# SCH_gaussian_cheap_2025-03-23.net
KiCad netlist of a schematic drawn in EasyEDA
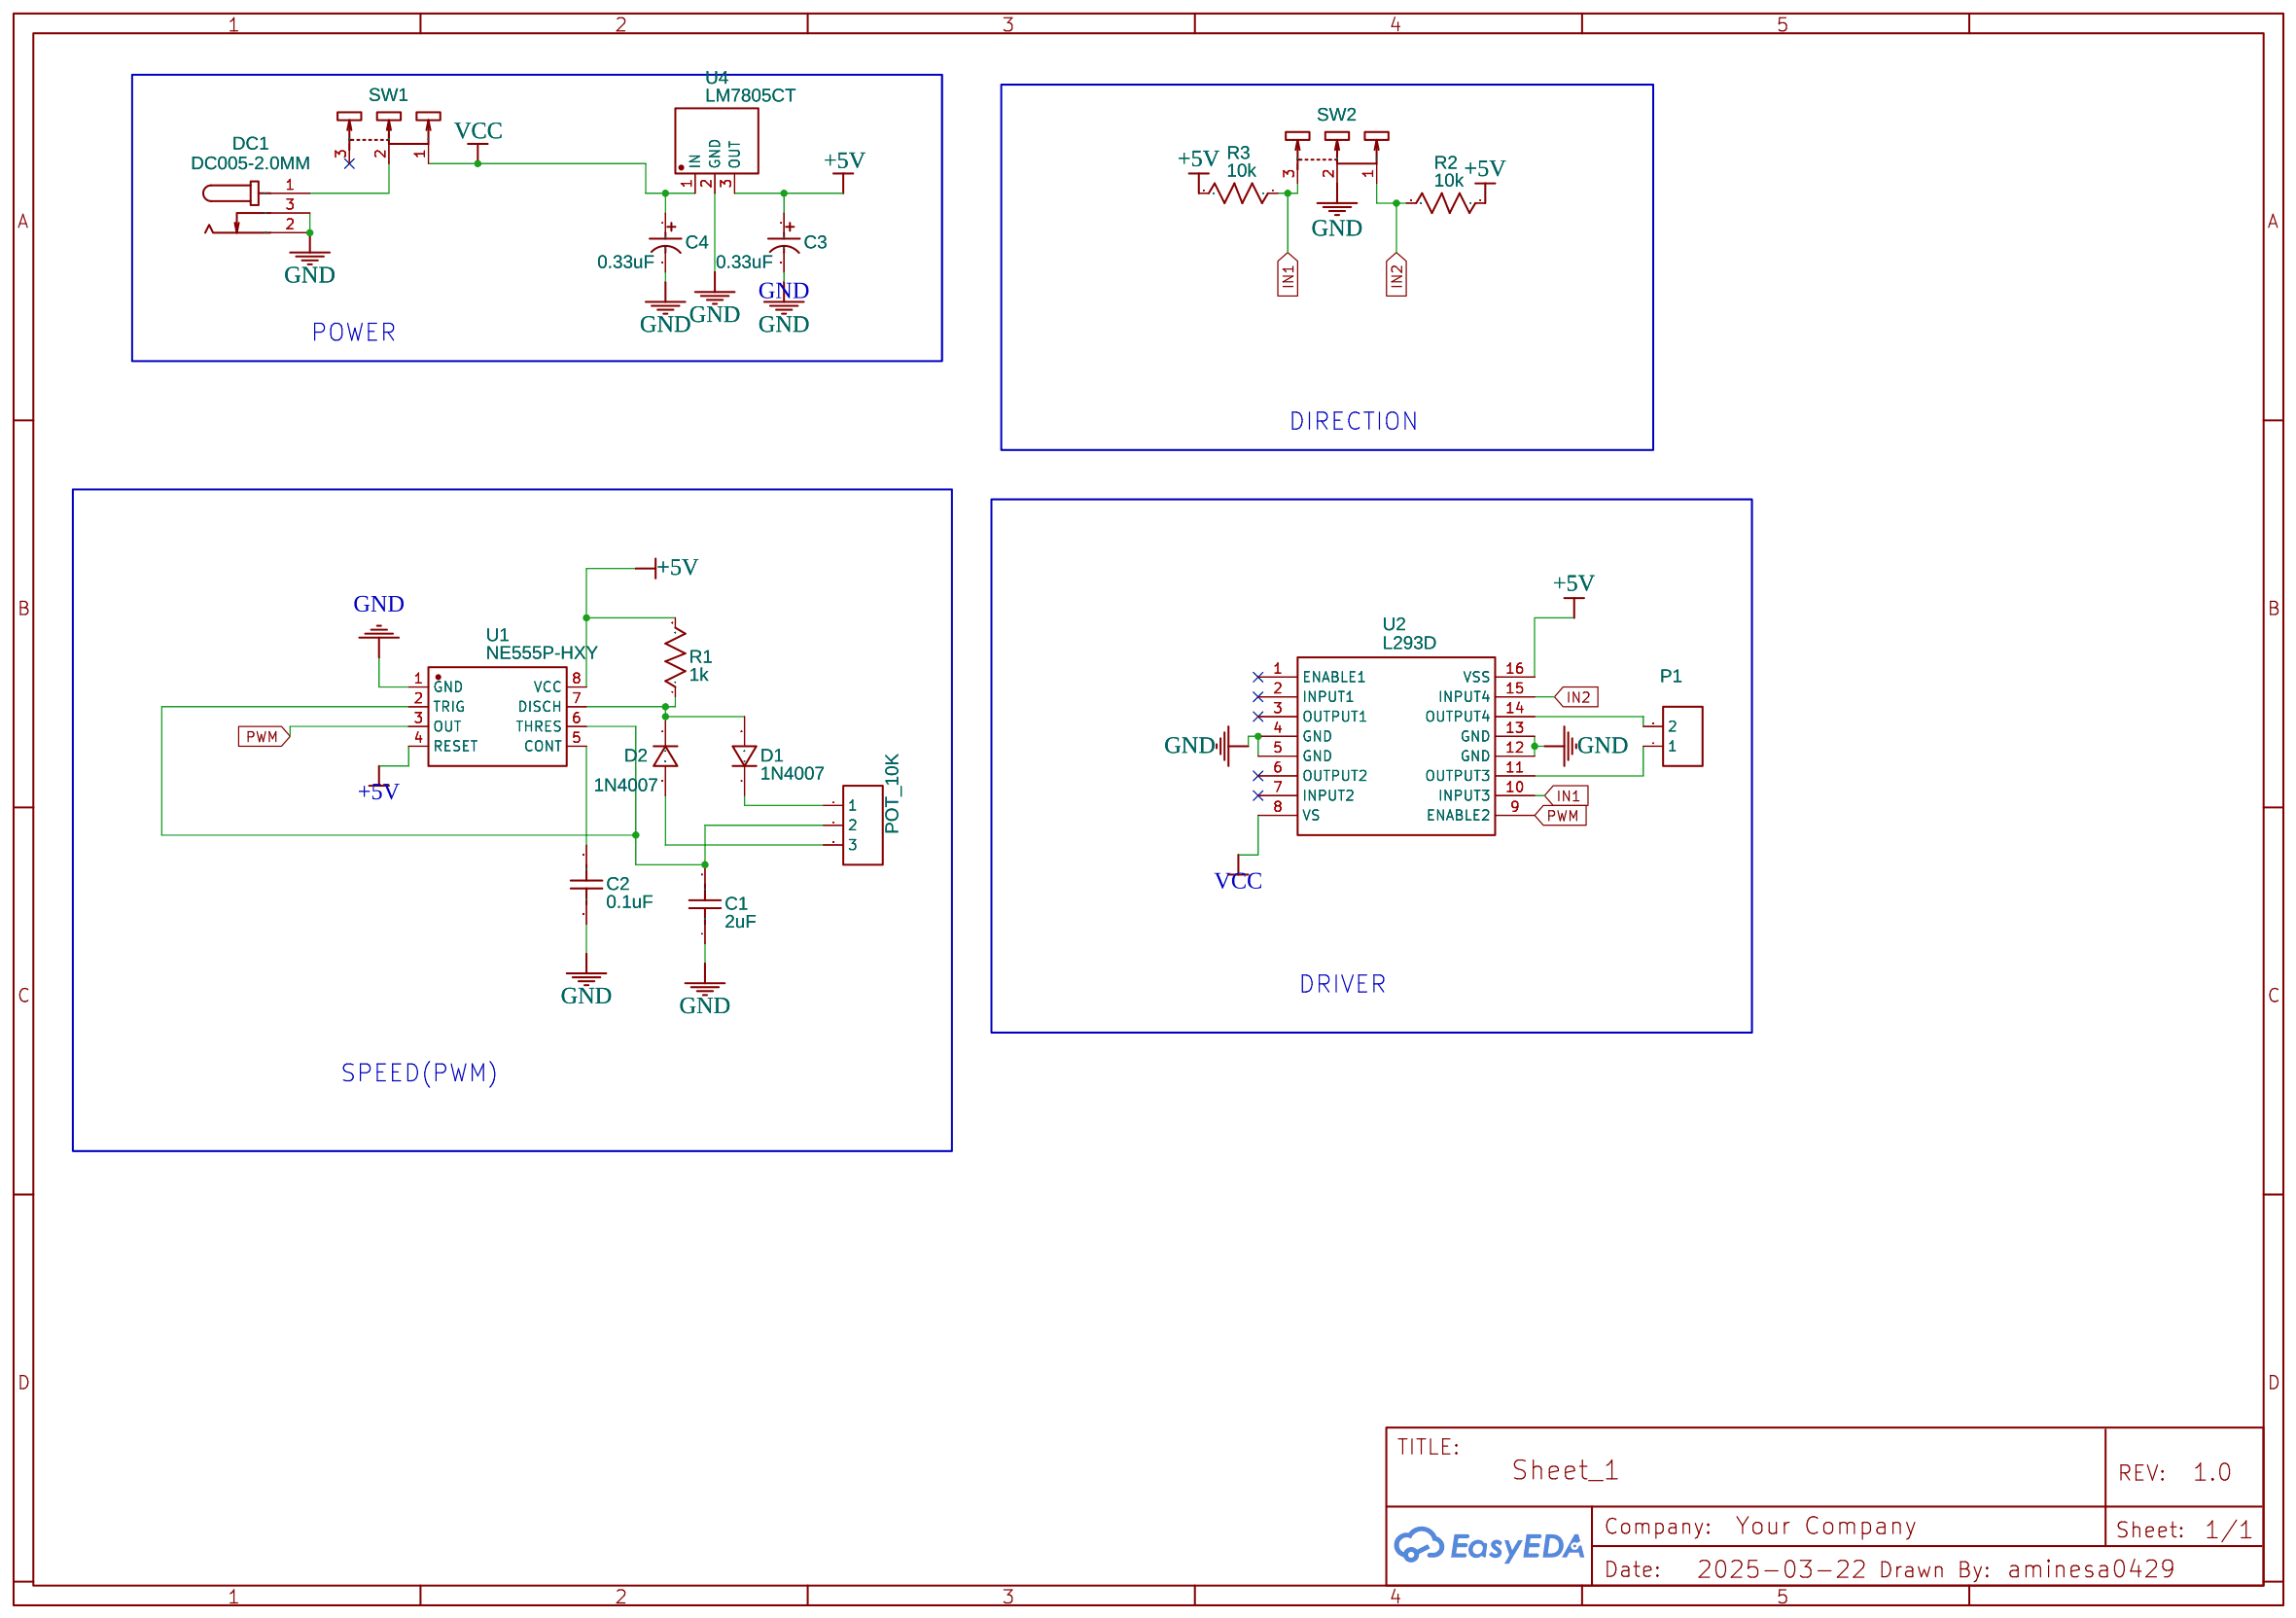
[diagram p0: schematic sheet]

(export (version "E")
  (design (tool "Eeschema 10.0.6"))
  (components
    (comp (ref "C1") (value "2uF") (libsource (lib "") (part "C_RAD-0.1_US")))
    (comp (ref "C2") (value "0.1uF") (libsource (lib "") (part "C_RAD-0.1_US")))
    (comp (ref "C3")
      (value "0.33uF")
      (fields (field (name "Manufacturer Part") "0.33uF 50V 5*11") (field (name "Manufacturer") "ValuePro"))
      (libsource (lib "") (part "0.33uF 50V 5*11"))
    )
    (comp (ref "C4")
      (value "0.33uF")
      (fields (field (name "Manufacturer Part") "0.33uF 50V 5*11") (field (name "Manufacturer") "ValuePro"))
      (libsource (lib "") (part "0.33uF 50V 5*11"))
    )
    (comp (ref "D1")
      (value "1N4007")
      (fields (field (name "Manufacturer") "SEMTECH"))
      (libsource (lib "") (part "1N4007_1"))
    )
    (comp (ref "D2")
      (value "1N4007")
      (fields (field (name "Manufacturer") "SEMTECH"))
      (libsource (lib "") (part "1N4007"))
    )
    (comp (ref "DC1")
      (value "DC005-2.0MM")
      (fields (field (name "Manufacturer") "SOFNG"))
      (libsource (lib "") (part "DC005-2.0MM"))
    )
    (comp (ref "P1") (value "CONN-TH_2P-P5.08") (libsource (lib "") (part "CONN-TH_2P-P5.08")))
    (comp (ref "POT_10K") (value "HDR-M-2.54_1x3") (libsource (lib "") (part "HDR-M-2.54_1x3")))
    (comp (ref "R1") (value "1k") (libsource (lib "") (part "R_AXIAL-0.5_US_1")))
    (comp (ref "R2") (value "10k") (libsource (lib "") (part "R_AXIAL-0.5_US")))
    (comp (ref "R3") (value "10k") (libsource (lib "") (part "R_AXIAL-0.5_US")))
    (comp (ref "SW1")
      (value "SLIDE-SWITCH-SPDT-125V-3A-4.7MM-180DEGR")
      (fields
        (field (name "Manufacturer Part") "SS-12D10L3")
        (field (name "Manufacturer") "XKB Connectivity(中国星坤)")
      )
      (libsource (lib "") (part "SLIDE-SWITCH-SPDT-125V-3A-4.7MM-180DEGR"))
    )
    (comp (ref "SW2")
      (value "SLIDE-SWITCH-SPDT-125V-3A-4.7MM-180DEGR")
      (fields
        (field (name "Manufacturer Part") "SS-12D10L3")
        (field (name "Manufacturer") "XKB Connectivity(中国星坤)")
      )
      (libsource (lib "") (part "SLIDE-SWITCH-SPDT-125V-3A-4.7MM-180DEGR"))
    )
    (comp (ref "U1")
      (value "NE555P-HXY")
      (fields (field (name "Manufacturer") "HXY MOSFET(华轩阳电子)"))
      (libsource (lib "") (part "NE555P-HXY"))
    )
    (comp (ref "U2")
      (value "L293D")
      (fields (field (name "Manufacturer") "ST(意法半导体)"))
      (libsource (lib "") (part "L293D"))
    )
    (comp (ref "U4")
      (value "LM7805CT")
      (fields (field (name "Manufacturer") "FAIRCHILD"))
      (libsource (lib "") (part "LM7805CT"))
    )
  )
  (nets
    (net (code "1") (name "+5V") (class "Default")
      (node (ref "C3") (pin "1") (pinfunction "1_1") (pintype "input"))
      (node (ref "R1") (pin "2") (pinfunction "2_2") (pintype "unspecified"))
      (node (ref "R2") (pin "1") (pinfunction "1_1") (pintype "unspecified"))
      (node (ref "R3") (pin "2") (pinfunction "2_2") (pintype "unspecified"))
      (node (ref "U1") (pin "4") (pinfunction "RESET_4") (pintype "unspecified"))
      (node (ref "U1") (pin "8") (pinfunction "VCC_8") (pintype "unspecified"))
      (node (ref "U2") (pin "16") (pinfunction "VSS_16") (pintype "unspecified"))
      (node (ref "U4") (pin "3") (pinfunction "OUT_3") (pintype "unspecified"))
    )
    (net (code "2") (name "GND") (class "Default")
      (node (ref "C1") (pin "1") (pinfunction "1_1") (pintype "unspecified"))
      (node (ref "C2") (pin "1") (pinfunction "1_1") (pintype "unspecified"))
      (node (ref "C3") (pin "2") (pinfunction "2_2") (pintype "input"))
      (node (ref "C4") (pin "2") (pinfunction "2_2") (pintype "input"))
      (node (ref "DC1") (pin "2") (pinfunction "2_2") (pintype "unspecified"))
      (node (ref "DC1") (pin "3") (pinfunction "3_3") (pintype "unspecified"))
      (node (ref "SW2") (pin "2") (pinfunction "2_2") (pintype "unspecified"))
      (node (ref "U1") (pin "1") (pinfunction "GND_1") (pintype "unspecified"))
      (node (ref "U2") (pin "12") (pinfunction "GND_12") (pintype "unspecified"))
      (node (ref "U2") (pin "13") (pinfunction "GND_13") (pintype "unspecified"))
      (node (ref "U2") (pin "4") (pinfunction "GND_4") (pintype "unspecified"))
      (node (ref "U2") (pin "5") (pinfunction "GND_5") (pintype "unspecified"))
      (node (ref "U4") (pin "2") (pinfunction "GND_2") (pintype "unspecified"))
    )
    (net (code "3") (name "IN1") (class "Default")
      (node (ref "R3") (pin "1") (pinfunction "1_1") (pintype "unspecified"))
      (node (ref "SW2") (pin "3") (pinfunction "3_3") (pintype "unspecified"))
      (node (ref "U2") (pin "10") (pinfunction "INPUT3_10") (pintype "unspecified"))
    )
    (net (code "4") (name "IN2") (class "Default")
      (node (ref "R2") (pin "2") (pinfunction "2_2") (pintype "unspecified"))
      (node (ref "SW2") (pin "1") (pinfunction "1_1") (pintype "unspecified"))
      (node (ref "U2") (pin "15") (pinfunction "INPUT4_15") (pintype "unspecified"))
    )
    (net (code "5") (name "Net-(D1-Pad1)") (class "Default")
      (node (ref "D1") (pin "1") (pinfunction "1_1") (pintype "unspecified"))
      (node (ref "POT_10K") (pin "1") (pinfunction "1_1") (pintype "input"))
    )
    (net (code "6") (name "Net-(D2-Pad2)") (class "Default")
      (node (ref "D2") (pin "2") (pinfunction "2_2") (pintype "unspecified"))
      (node (ref "POT_10K") (pin "3") (pinfunction "3_3") (pintype "input"))
    )
    (net (code "7") (name "Net-(DC1-Pad1)") (class "Default")
      (node (ref "DC1") (pin "1") (pinfunction "1_1") (pintype "unspecified"))
      (node (ref "SW1") (pin "2") (pinfunction "2_2") (pintype "unspecified"))
    )
    (net (code "8") (name "Net-(U1-CONT)") (class "Default")
      (node (ref "C2") (pin "2") (pinfunction "2_2") (pintype "unspecified"))
      (node (ref "U1") (pin "5") (pinfunction "CONT_5") (pintype "unspecified"))
    )
    (net (code "9") (name "Net-(U1-DISCH)") (class "Default")
      (node (ref "D1") (pin "2") (pinfunction "2_2") (pintype "unspecified"))
      (node (ref "D2") (pin "1") (pinfunction "1_1") (pintype "unspecified"))
      (node (ref "R1") (pin "1") (pinfunction "1_1") (pintype "unspecified"))
      (node (ref "U1") (pin "7") (pinfunction "DISCH_7") (pintype "unspecified"))
    )
    (net (code "10") (name "Net-(U1-THRES)") (class "Default")
      (node (ref "C1") (pin "2") (pinfunction "2_2") (pintype "unspecified"))
      (node (ref "POT_10K") (pin "2") (pinfunction "2_2") (pintype "input"))
      (node (ref "U1") (pin "2") (pinfunction "TRIG_2") (pintype "unspecified"))
      (node (ref "U1") (pin "6") (pinfunction "THRES_6") (pintype "unspecified"))
    )
    (net (code "11") (name "Net-(U2-OUTPUT3)") (class "Default")
      (node (ref "P1") (pin "1") (pinfunction "1_1") (pintype "unspecified"))
      (node (ref "U2") (pin "11") (pinfunction "OUTPUT3_11") (pintype "unspecified"))
    )
    (net (code "12") (name "Net-(U2-OUTPUT4)") (class "Default")
      (node (ref "P1") (pin "2") (pinfunction "2_2") (pintype "unspecified"))
      (node (ref "U2") (pin "14") (pinfunction "OUTPUT4_14") (pintype "unspecified"))
    )
    (net (code "13") (name "PWM") (class "Default")
      (node (ref "U1") (pin "3") (pinfunction "OUT_3") (pintype "unspecified"))
      (node (ref "U2") (pin "9") (pinfunction "ENABLE2_9") (pintype "unspecified"))
    )
    (net (code "14") (name "VCC") (class "Default")
      (node (ref "C4") (pin "1") (pinfunction "1_1") (pintype "input"))
      (node (ref "SW1") (pin "1") (pinfunction "1_1") (pintype "unspecified"))
      (node (ref "U2") (pin "8") (pinfunction "VS_8") (pintype "unspecified"))
      (node (ref "U4") (pin "1") (pinfunction "IN_1") (pintype "unspecified"))
    )
    (net (code "15") (name "unconnected-(SW1-Pad3)") (class "Default")
      (node (ref "SW1") (pin "3") (pinfunction "3_3") (pintype "unspecified+no_connect"))
    )
    (net (code "16") (name "unconnected-(U2-ENABLE1-Pad1)") (class "Default")
      (node (ref "U2") (pin "1") (pinfunction "ENABLE1_1") (pintype "unspecified+no_connect"))
    )
    (net (code "17") (name "unconnected-(U2-INPUT1-Pad2)") (class "Default")
      (node (ref "U2") (pin "2") (pinfunction "INPUT1_2") (pintype "unspecified+no_connect"))
    )
    (net (code "18") (name "unconnected-(U2-INPUT2-Pad7)") (class "Default")
      (node (ref "U2") (pin "7") (pinfunction "INPUT2_7") (pintype "unspecified+no_connect"))
    )
    (net (code "19") (name "unconnected-(U2-OUTPUT1-Pad3)") (class "Default")
      (node (ref "U2") (pin "3") (pinfunction "OUTPUT1_3") (pintype "unspecified+no_connect"))
    )
    (net (code "20") (name "unconnected-(U2-OUTPUT2-Pad6)") (class "Default")
      (node (ref "U2") (pin "6") (pinfunction "OUTPUT2_6") (pintype "unspecified+no_connect"))
    )
  )
)
